# SCH_VFD_Driver_PT6315_2025-07-27.net
KiCad netlist of a schematic drawn in EasyEDA
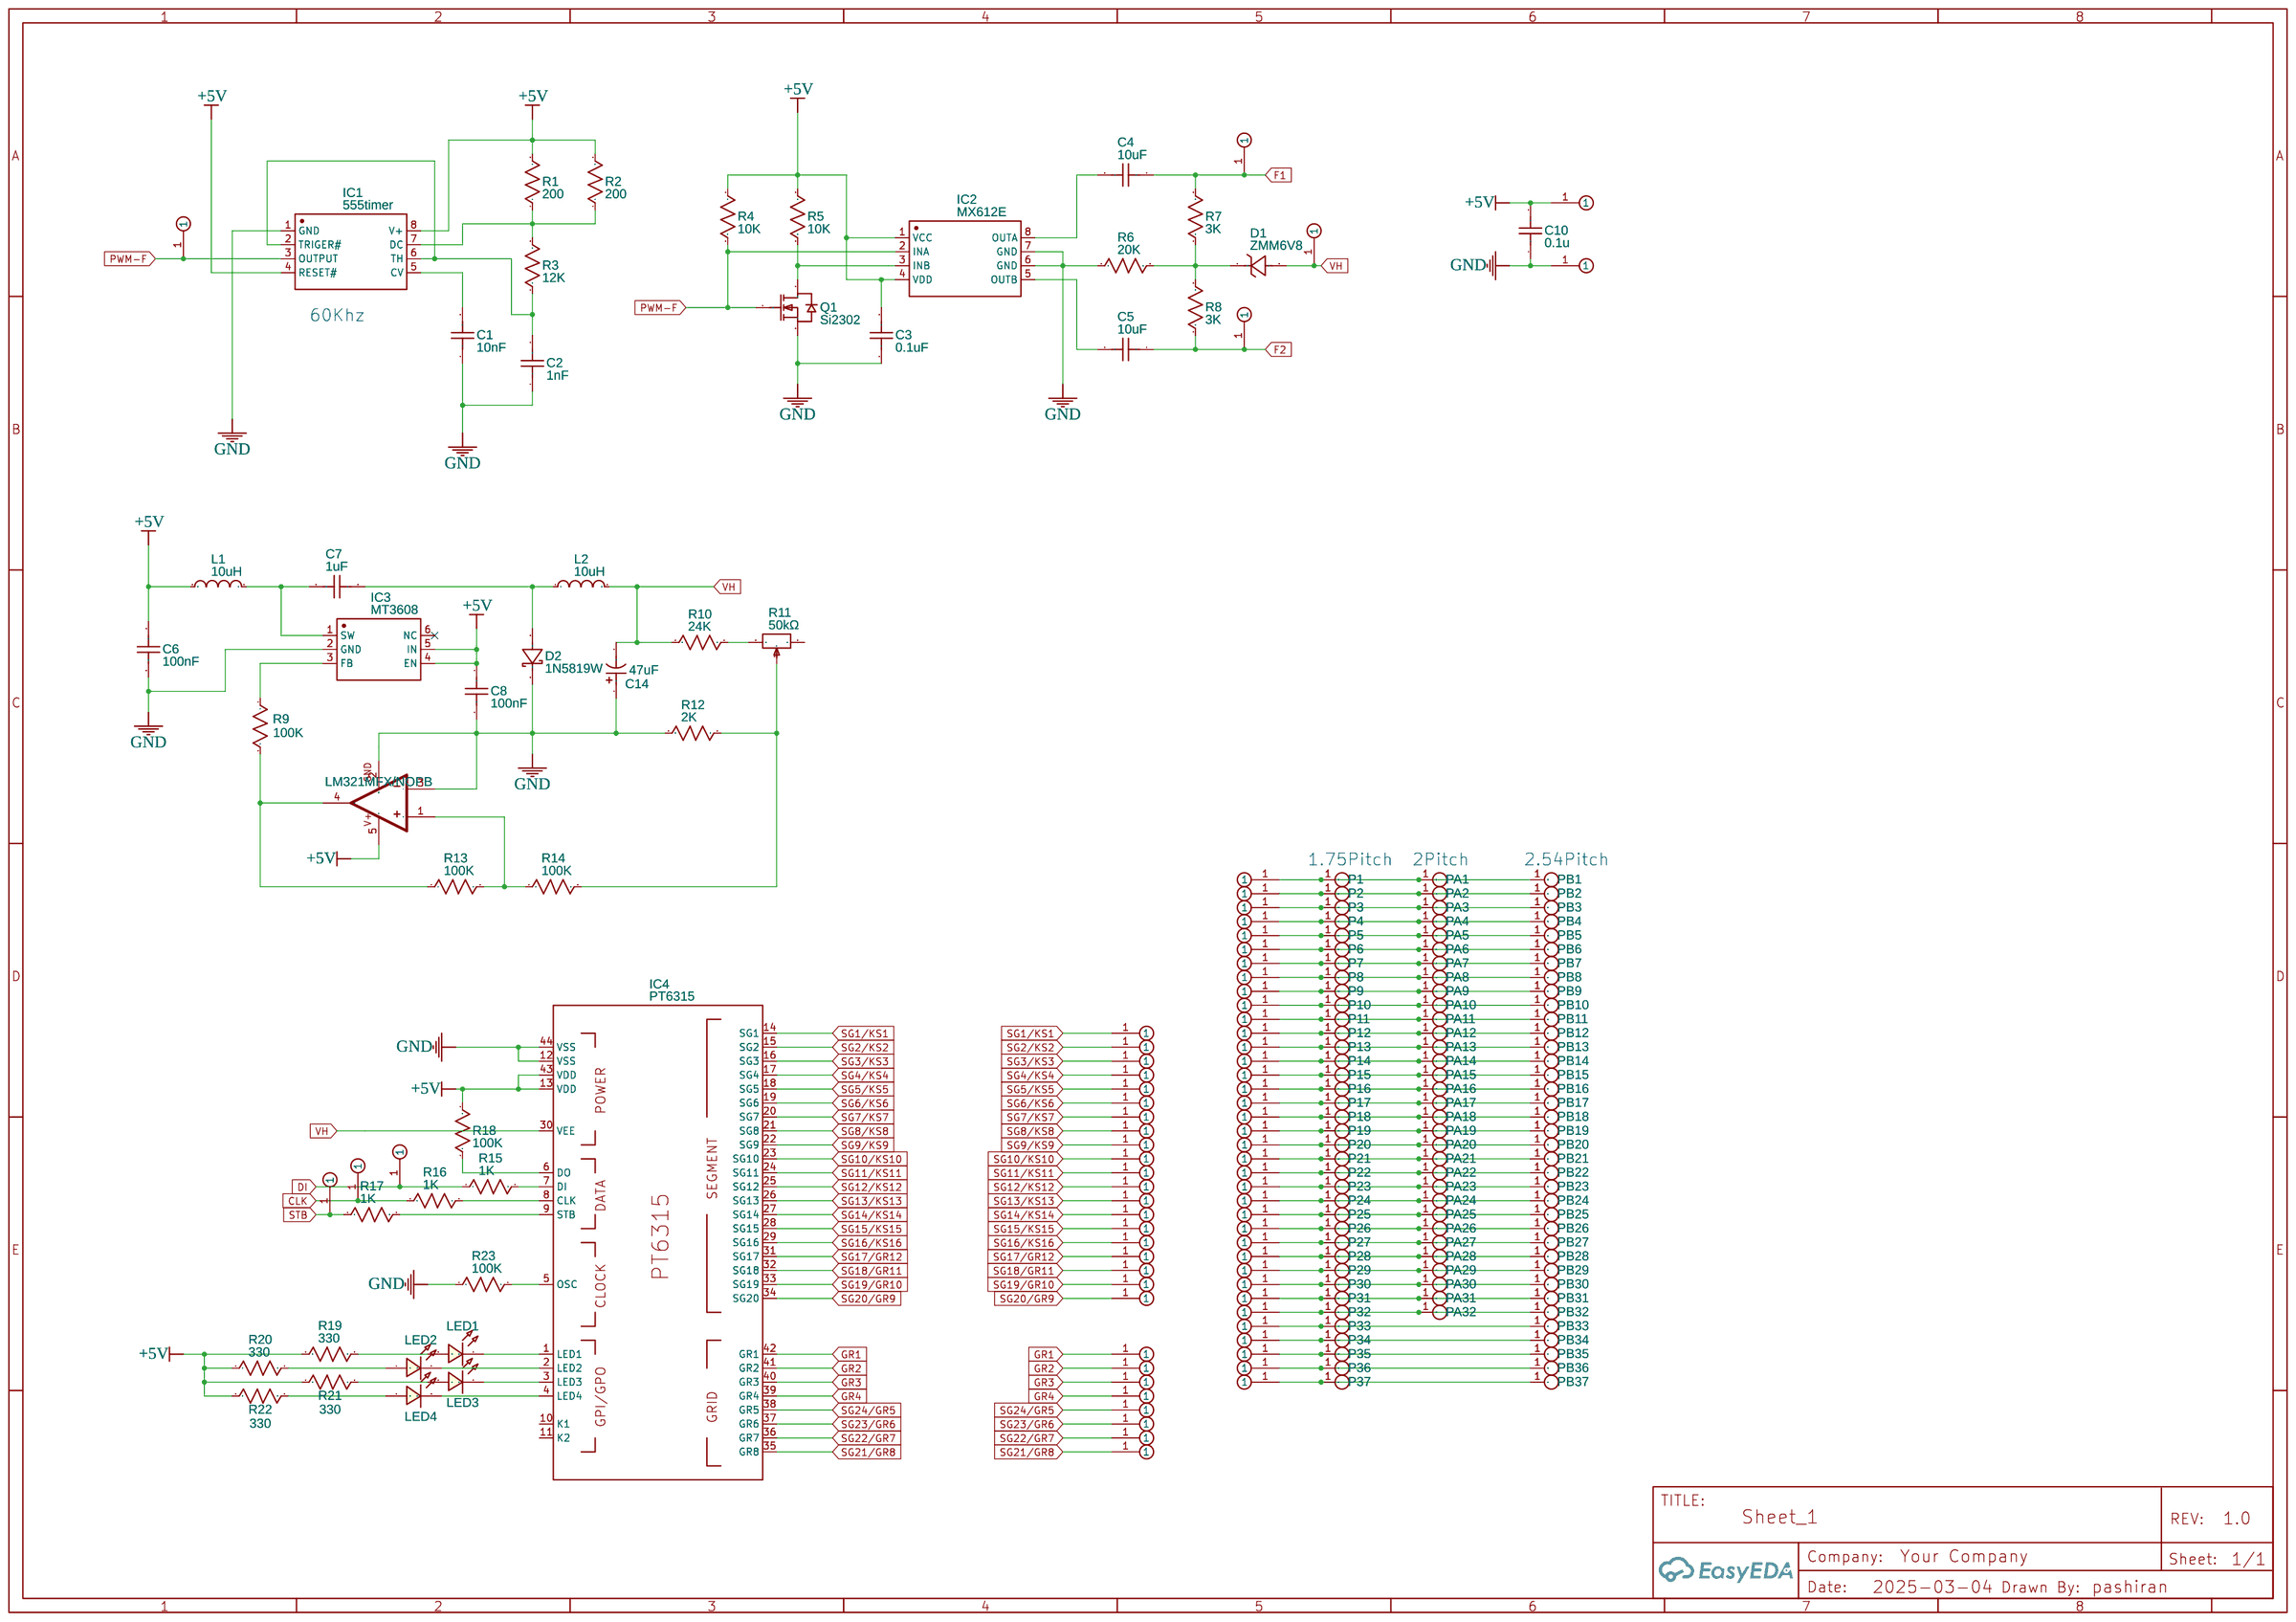
[diagram p0: schematic sheet]

(export (version "E")
  (design (tool "Eeschema 10.0.6"))
  (components
    (comp (ref "C1") (value "10nF") (libsource (lib "") (part "C_0805_US")))
    (comp (ref "C2") (value "1nF") (libsource (lib "") (part "C_0805_US")))
    (comp (ref "C3") (value "0.1uF") (libsource (lib "") (part "C_0805_US")))
    (comp (ref "C4") (value "10uF") (libsource (lib "") (part "C_0805_US_3")))
    (comp (ref "C5") (value "10uF") (libsource (lib "") (part "C_0805_US_3")))
    (comp (ref "C6") (value "100nF") (libsource (lib "") (part "C_0805_US_2")))
    (comp (ref "C7") (value "1uF") (libsource (lib "") (part "C_0805_US_1")))
    (comp (ref "C8") (value "100nF") (libsource (lib "") (part "C_0805_US_2")))
    (comp (ref "C10") (value "0.1u") (libsource (lib "") (part "C_0805_US")))
    (comp (ref "C14")
      (value "47uF")
      (fields
        (field (name "Manufacturer Part") "FVH025ADA470M0654")
        (field (name "Manufacturer") "FOSAN(富捷/富信)")
      )
      (libsource (lib "") (part "FVH025ADA470M0654"))
    )
    (comp (ref "CLK") (value "SMD-PAD-Mini") (libsource (lib "") (part "SMD-PAD-Mini_7")))
    (comp (ref "D1")
      (value "ZMM6V8")
      (fields (field (name "Manufacturer") "HXY MOSFET(华轩阳电子)"))
      (libsource (lib "") (part "ZMM6V8_C5345995"))
    )
    (comp (ref "D2")
      (value "1N5819W")
      (fields (field (name "Manufacturer") "ZHIDE(志得)"))
      (libsource (lib "") (part "1N5819W_C2683619"))
    )
    (comp (ref "DI") (value "SMD-PAD-Mini") (libsource (lib "") (part "SMD-PAD-Mini_3")))
    (comp (ref "F1") (value "SMD-PAD-Mini") (libsource (lib "") (part "SMD-PAD-Mini_6")))
    (comp (ref "F2") (value "SMD-PAD-Mini") (libsource (lib "") (part "SMD-PAD-Mini_6")))
    (comp (ref "GND") (value "SMD-PAD-Mini") (libsource (lib "") (part "SMD-PAD-Mini_4")))
    (comp (ref "IC1")
      (value "555timer")
      (fields (field (name "Manufacturer Part") "LMC555CMX/NOPB") (field (name "Manufacturer") "TI(德州仪器)"))
      (libsource (lib "") (part "LMC555CMX/NOPB"))
    )
    (comp (ref "IC2")
      (value "MX612E")
      (fields (field (name "Manufacturer") "Mixic(中科芯亿达)"))
      (libsource (lib "") (part "MX612E"))
    )
    (comp (ref "IC3")
      (value "MT3608")
      (fields (field (name "Manufacturer") "西安航天民芯"))
      (libsource (lib "") (part "MT3608"))
    )
    (comp (ref "IC4") (value "PT6315") (libsource (lib "") (part "PT6315")))
    (comp (ref "L1")
      (value "10uH")
      (fields (field (name "Manufacturer Part") "SMMS0420-100M") (field (name "Manufacturer") "SXN(顺翔诺)"))
      (libsource (lib "") (part "SMMS0420-100M_1"))
    )
    (comp (ref "L2")
      (value "10uH")
      (fields (field (name "Manufacturer Part") "SMMS0420-100M") (field (name "Manufacturer") "SXN(顺翔诺)"))
      (libsource (lib "") (part "SMMS0420-100M"))
    )
    (comp (ref "LED1")
      (value "LED-0805_R")
      (fields
        (field (name "Manufacturer Part") "17-21SURC/S530-A3/TR8")
        (field (name "Manufacturer") "EVERLIGHT(台湾亿光)")
      )
      (libsource (lib "") (part "LED-0805_R"))
    )
    (comp (ref "LED2")
      (value "LED-0805_R")
      (fields
        (field (name "Manufacturer Part") "17-21SURC/S530-A3/TR8")
        (field (name "Manufacturer") "EVERLIGHT(台湾亿光)")
      )
      (libsource (lib "") (part "LED-0805_R"))
    )
    (comp (ref "LED3")
      (value "LED-0805_R")
      (fields
        (field (name "Manufacturer Part") "17-21SURC/S530-A3/TR8")
        (field (name "Manufacturer") "EVERLIGHT(台湾亿光)")
      )
      (libsource (lib "") (part "LED-0805_R"))
    )
    (comp (ref "LED4")
      (value "LED-0805_R")
      (fields
        (field (name "Manufacturer Part") "17-21SURC/S530-A3/TR8")
        (field (name "Manufacturer") "EVERLIGHT(台湾亿光)")
      )
      (libsource (lib "") (part "LED-0805_R"))
    )
    (comp (ref "P1") (value "CON PAD") (libsource (lib "") (part "CON PAD_2")))
    (comp (ref "P2") (value "CON PAD") (libsource (lib "") (part "CON PAD_2")))
    (comp (ref "P3") (value "CON PAD") (libsource (lib "") (part "CON PAD_2")))
    (comp (ref "P4") (value "CON PAD") (libsource (lib "") (part "CON PAD_2")))
    (comp (ref "P5") (value "CON PAD") (libsource (lib "") (part "CON PAD_2")))
    (comp (ref "P6") (value "CON PAD") (libsource (lib "") (part "CON PAD_2")))
    (comp (ref "P7") (value "CON PAD") (libsource (lib "") (part "CON PAD_2")))
    (comp (ref "P8") (value "CON PAD") (libsource (lib "") (part "CON PAD_2")))
    (comp (ref "P9") (value "CON PAD") (libsource (lib "") (part "CON PAD_2")))
    (comp (ref "P10") (value "CON PAD") (libsource (lib "") (part "CON PAD_2")))
    (comp (ref "P11") (value "CON PAD") (libsource (lib "") (part "CON PAD_2")))
    (comp (ref "P12") (value "CON PAD") (libsource (lib "") (part "CON PAD_2")))
    (comp (ref "P13") (value "CON PAD") (libsource (lib "") (part "CON PAD_2")))
    (comp (ref "P14") (value "CON PAD") (libsource (lib "") (part "CON PAD_2")))
    (comp (ref "P15") (value "CON PAD") (libsource (lib "") (part "CON PAD_2")))
    (comp (ref "P16") (value "CON PAD") (libsource (lib "") (part "CON PAD_2")))
    (comp (ref "P17") (value "CON PAD") (libsource (lib "") (part "CON PAD_2")))
    (comp (ref "P18") (value "CON PAD") (libsource (lib "") (part "CON PAD_2")))
    (comp (ref "P19") (value "CON PAD") (libsource (lib "") (part "CON PAD_2")))
    (comp (ref "P20") (value "CON PAD") (libsource (lib "") (part "CON PAD_2")))
    (comp (ref "P21") (value "CON PAD") (libsource (lib "") (part "CON PAD_2")))
    (comp (ref "P22") (value "CON PAD") (libsource (lib "") (part "CON PAD_2")))
    (comp (ref "P23") (value "CON PAD") (libsource (lib "") (part "CON PAD_2")))
    (comp (ref "P24") (value "CON PAD") (libsource (lib "") (part "CON PAD_2")))
    (comp (ref "P25") (value "CON PAD") (libsource (lib "") (part "CON PAD_2")))
    (comp (ref "P26") (value "CON PAD") (libsource (lib "") (part "CON PAD_2")))
    (comp (ref "P27") (value "CON PAD") (libsource (lib "") (part "CON PAD_2")))
    (comp (ref "P28") (value "CON PAD") (libsource (lib "") (part "CON PAD_2")))
    (comp (ref "P29") (value "CON PAD") (libsource (lib "") (part "CON PAD_2")))
    (comp (ref "P30") (value "CON PAD") (libsource (lib "") (part "CON PAD_2")))
    (comp (ref "P31") (value "CON PAD") (libsource (lib "") (part "CON PAD_2")))
    (comp (ref "P32") (value "CON PAD") (libsource (lib "") (part "CON PAD_2")))
    (comp (ref "P33") (value "CON PAD") (libsource (lib "") (part "CON PAD_2")))
    (comp (ref "P34") (value "CON PAD") (libsource (lib "") (part "CON PAD_2")))
    (comp (ref "P35") (value "CON PAD") (libsource (lib "") (part "CON PAD_2")))
    (comp (ref "P36") (value "CON PAD") (libsource (lib "") (part "CON PAD_2")))
    (comp (ref "P37") (value "CON PAD") (libsource (lib "") (part "CON PAD_2")))
    (comp (ref "PA1") (value "CON PAD") (libsource (lib "") (part "CON PAD")))
    (comp (ref "PA2") (value "CON PAD") (libsource (lib "") (part "CON PAD")))
    (comp (ref "PA3") (value "CON PAD") (libsource (lib "") (part "CON PAD")))
    (comp (ref "PA4") (value "CON PAD") (libsource (lib "") (part "CON PAD")))
    (comp (ref "PA5") (value "CON PAD") (libsource (lib "") (part "CON PAD")))
    (comp (ref "PA6") (value "CON PAD") (libsource (lib "") (part "CON PAD")))
    (comp (ref "PA7") (value "CON PAD") (libsource (lib "") (part "CON PAD")))
    (comp (ref "PA8") (value "CON PAD") (libsource (lib "") (part "CON PAD")))
    (comp (ref "PA9") (value "CON PAD") (libsource (lib "") (part "CON PAD")))
    (comp (ref "PA10") (value "CON PAD") (libsource (lib "") (part "CON PAD")))
    (comp (ref "PA11") (value "CON PAD") (libsource (lib "") (part "CON PAD")))
    (comp (ref "PA12") (value "CON PAD") (libsource (lib "") (part "CON PAD")))
    (comp (ref "PA13") (value "CON PAD") (libsource (lib "") (part "CON PAD")))
    (comp (ref "PA14") (value "CON PAD") (libsource (lib "") (part "CON PAD")))
    (comp (ref "PA15") (value "CON PAD") (libsource (lib "") (part "CON PAD")))
    (comp (ref "PA16") (value "CON PAD") (libsource (lib "") (part "CON PAD")))
    (comp (ref "PA17") (value "CON PAD") (libsource (lib "") (part "CON PAD")))
    (comp (ref "PA18") (value "CON PAD") (libsource (lib "") (part "CON PAD")))
    (comp (ref "PA19") (value "CON PAD") (libsource (lib "") (part "CON PAD")))
    (comp (ref "PA20") (value "CON PAD") (libsource (lib "") (part "CON PAD")))
    (comp (ref "PA21") (value "CON PAD") (libsource (lib "") (part "CON PAD")))
    (comp (ref "PA22") (value "CON PAD") (libsource (lib "") (part "CON PAD")))
    (comp (ref "PA23") (value "CON PAD") (libsource (lib "") (part "CON PAD")))
    (comp (ref "PA24") (value "CON PAD") (libsource (lib "") (part "CON PAD")))
    (comp (ref "PA25") (value "CON PAD") (libsource (lib "") (part "CON PAD")))
    (comp (ref "PA26") (value "CON PAD") (libsource (lib "") (part "CON PAD")))
    (comp (ref "PA27") (value "CON PAD") (libsource (lib "") (part "CON PAD")))
    (comp (ref "PA28") (value "CON PAD") (libsource (lib "") (part "CON PAD")))
    (comp (ref "PA29") (value "CON PAD") (libsource (lib "") (part "CON PAD")))
    (comp (ref "PA30") (value "CON PAD") (libsource (lib "") (part "CON PAD")))
    (comp (ref "PA31") (value "CON PAD") (libsource (lib "") (part "CON PAD")))
    (comp (ref "PA32") (value "CON PAD") (libsource (lib "") (part "CON PAD")))
    (comp (ref "PB1") (value "CON PAD") (libsource (lib "") (part "CON PAD_1")))
    (comp (ref "PB2") (value "CON PAD") (libsource (lib "") (part "CON PAD_1")))
    (comp (ref "PB3") (value "CON PAD") (libsource (lib "") (part "CON PAD_1")))
    (comp (ref "PB4") (value "CON PAD") (libsource (lib "") (part "CON PAD_1")))
    (comp (ref "PB5") (value "CON PAD") (libsource (lib "") (part "CON PAD_1")))
    (comp (ref "PB6") (value "CON PAD") (libsource (lib "") (part "CON PAD_1")))
    (comp (ref "PB7") (value "CON PAD") (libsource (lib "") (part "CON PAD_1")))
    (comp (ref "PB8") (value "CON PAD") (libsource (lib "") (part "CON PAD_1")))
    (comp (ref "PB9") (value "CON PAD") (libsource (lib "") (part "CON PAD_1")))
    (comp (ref "PB10") (value "CON PAD") (libsource (lib "") (part "CON PAD_1")))
    (comp (ref "PB11") (value "CON PAD") (libsource (lib "") (part "CON PAD_1")))
    (comp (ref "PB12") (value "CON PAD") (libsource (lib "") (part "CON PAD_1")))
    (comp (ref "PB13") (value "CON PAD") (libsource (lib "") (part "CON PAD_1")))
    (comp (ref "PB14") (value "CON PAD") (libsource (lib "") (part "CON PAD_1")))
    (comp (ref "PB15") (value "CON PAD") (libsource (lib "") (part "CON PAD_1")))
    (comp (ref "PB16") (value "CON PAD") (libsource (lib "") (part "CON PAD_1")))
    (comp (ref "PB17") (value "CON PAD") (libsource (lib "") (part "CON PAD_1")))
    (comp (ref "PB18") (value "CON PAD") (libsource (lib "") (part "CON PAD_1")))
    (comp (ref "PB19") (value "CON PAD") (libsource (lib "") (part "CON PAD_1")))
    (comp (ref "PB20") (value "CON PAD") (libsource (lib "") (part "CON PAD_1")))
    (comp (ref "PB21") (value "CON PAD") (libsource (lib "") (part "CON PAD_1")))
    (comp (ref "PB22") (value "CON PAD") (libsource (lib "") (part "CON PAD_1")))
    (comp (ref "PB23") (value "CON PAD") (libsource (lib "") (part "CON PAD_1")))
    (comp (ref "PB24") (value "CON PAD") (libsource (lib "") (part "CON PAD_1")))
    (comp (ref "PB25") (value "CON PAD") (libsource (lib "") (part "CON PAD_1")))
    (comp (ref "PB26") (value "CON PAD") (libsource (lib "") (part "CON PAD_1")))
    (comp (ref "PB27") (value "CON PAD") (libsource (lib "") (part "CON PAD_1")))
    (comp (ref "PB28") (value "CON PAD") (libsource (lib "") (part "CON PAD_1")))
    (comp (ref "PB29") (value "CON PAD") (libsource (lib "") (part "CON PAD_1")))
    (comp (ref "PB30") (value "CON PAD") (libsource (lib "") (part "CON PAD_1")))
    (comp (ref "PB31") (value "CON PAD") (libsource (lib "") (part "CON PAD_1")))
    (comp (ref "PB32") (value "CON PAD") (libsource (lib "") (part "CON PAD_1")))
    (comp (ref "PB33") (value "CON PAD") (libsource (lib "") (part "CON PAD_1")))
    (comp (ref "PB34") (value "CON PAD") (libsource (lib "") (part "CON PAD_1")))
    (comp (ref "PB35") (value "CON PAD") (libsource (lib "") (part "CON PAD_1")))
    (comp (ref "PB36") (value "CON PAD") (libsource (lib "") (part "CON PAD_1")))
    (comp (ref "PB37") (value "CON PAD") (libsource (lib "") (part "CON PAD_1")))
    (comp (ref "PWM") (value "SMD-PAD-Mini") (libsource (lib "") (part "SMD-PAD-Mini_9")))
    (comp (ref "Q1")
      (value "Si2302")
      (fields
        (field (name "Manufacturer Part") "Si2302CDS-T1-GE3")
        (field (name "Manufacturer") "VISHAY(威世)")
      )
      (libsource (lib "") (part "Si2302CDS-T1-GE3"))
    )
    (comp (ref "R1") (value "200") (libsource (lib "") (part "R_0805_US")))
    (comp (ref "R2") (value "200") (libsource (lib "") (part "R_0805_US")))
    (comp (ref "R3") (value "12K") (libsource (lib "") (part "R_0805_US")))
    (comp (ref "R4") (value "10K") (libsource (lib "") (part "R_0805_US_1")))
    (comp (ref "R5") (value "10K") (libsource (lib "") (part "R_0805_US_1")))
    (comp (ref "R6") (value "20K") (libsource (lib "") (part "R_0805_US_2")))
    (comp (ref "R7") (value "3K") (libsource (lib "") (part "R_0805_US")))
    (comp (ref "R8") (value "3K") (libsource (lib "") (part "R_0805_US")))
    (comp (ref "R9") (value "100K") (libsource (lib "") (part "R_0805_US_1")))
    (comp (ref "R10") (value "24K") (libsource (lib "") (part "R_0805_US_2")))
    (comp (ref "R11")
      (value "50kΩ")
      (fields (field (name "Manufacturer Part") "VG039NCHXTB503") (field (name "Manufacturer") "HDK(北陆电气)"))
      (libsource (lib "") (part "VG039NCHXTB503"))
    )
    (comp (ref "R12") (value "2K") (libsource (lib "") (part "R_0805_US_3")))
    (comp (ref "R13") (value "100K") (libsource (lib "") (part "R_0805_US_2")))
    (comp (ref "R14") (value "100K") (libsource (lib "") (part "R_0805_US_2")))
    (comp (ref "R15") (value "1K") (libsource (lib "") (part "R_0805_US_2")))
    (comp (ref "R16") (value "1K") (libsource (lib "") (part "R_0805_US_2")))
    (comp (ref "R17") (value "1K") (libsource (lib "") (part "R_0805_US_2")))
    (comp (ref "R18") (value "100K") (libsource (lib "") (part "R_0805_US")))
    (comp (ref "R19") (value "330") (libsource (lib "") (part "R_0805_US_2")))
    (comp (ref "R20") (value "330") (libsource (lib "") (part "R_0805_US_2")))
    (comp (ref "R21") (value "330") (libsource (lib "") (part "R_0805_US_2")))
    (comp (ref "R22") (value "330") (libsource (lib "") (part "R_0805_US_2")))
    (comp (ref "R23") (value "100K") (libsource (lib "") (part "R_0805_US_2")))
    (comp (ref "STB") (value "SMD-PAD-Mini") (libsource (lib "") (part "SMD-PAD-Mini_5")))
    (comp (ref "U1") (value "SMD-PAD-Mini") (libsource (lib "") (part "SMD-PAD-Mini_1")))
    (comp (ref "U2") (value "SMD-PAD-Mini") (libsource (lib "") (part "SMD-PAD-Mini_1")))
    (comp (ref "U3") (value "SMD-PAD-Mini") (libsource (lib "") (part "SMD-PAD-Mini_1")))
    (comp (ref "U4") (value "SMD-PAD-Mini") (libsource (lib "") (part "SMD-PAD-Mini_1")))
    (comp (ref "U5") (value "SMD-PAD-Mini") (libsource (lib "") (part "SMD-PAD-Mini_1")))
    (comp (ref "U6") (value "SMD-PAD-Mini") (libsource (lib "") (part "SMD-PAD-Mini_1")))
    (comp (ref "U7") (value "SMD-PAD-Mini") (libsource (lib "") (part "SMD-PAD-Mini_1")))
    (comp (ref "U8") (value "SMD-PAD-Mini") (libsource (lib "") (part "SMD-PAD-Mini_1")))
    (comp (ref "U9") (value "SMD-PAD-Mini") (libsource (lib "") (part "SMD-PAD-Mini_1")))
    (comp (ref "U10") (value "SMD-PAD-Mini") (libsource (lib "") (part "SMD-PAD-Mini_1")))
    (comp (ref "U11") (value "SMD-PAD-Mini") (libsource (lib "") (part "SMD-PAD-Mini_1")))
    (comp (ref "U12") (value "SMD-PAD-Mini") (libsource (lib "") (part "SMD-PAD-Mini_1")))
    (comp (ref "U13") (value "SMD-PAD-Mini") (libsource (lib "") (part "SMD-PAD-Mini_1")))
    (comp (ref "U14") (value "SMD-PAD-Mini") (libsource (lib "") (part "SMD-PAD-Mini_1")))
    (comp (ref "U15") (value "SMD-PAD-Mini") (libsource (lib "") (part "SMD-PAD-Mini_1")))
    (comp (ref "U16") (value "SMD-PAD-Mini") (libsource (lib "") (part "SMD-PAD-Mini_1")))
    (comp (ref "U17") (value "SMD-PAD-Mini") (libsource (lib "") (part "SMD-PAD-Mini_1")))
    (comp (ref "U18") (value "SMD-PAD-Mini") (libsource (lib "") (part "SMD-PAD-Mini_1")))
    (comp (ref "U19") (value "SMD-PAD-Mini") (libsource (lib "") (part "SMD-PAD-Mini_1")))
    (comp (ref "U20") (value "SMD-PAD-Mini") (libsource (lib "") (part "SMD-PAD-Mini_1")))
    (comp (ref "U21") (value "SMD-PAD-Mini") (libsource (lib "") (part "SMD-PAD-Mini_1")))
    (comp (ref "U22") (value "SMD-PAD-Mini") (libsource (lib "") (part "SMD-PAD-Mini_1")))
    (comp (ref "U23") (value "SMD-PAD-Mini") (libsource (lib "") (part "SMD-PAD-Mini_1")))
    (comp (ref "U24") (value "SMD-PAD-Mini") (libsource (lib "") (part "SMD-PAD-Mini_1")))
    (comp (ref "U25") (value "SMD-PAD-Mini") (libsource (lib "") (part "SMD-PAD-Mini_1")))
    (comp (ref "U26") (value "SMD-PAD-Mini") (libsource (lib "") (part "SMD-PAD-Mini_1")))
    (comp (ref "U27") (value "SMD-PAD-Mini") (libsource (lib "") (part "SMD-PAD-Mini_1")))
    (comp (ref "U28") (value "SMD-PAD-Mini") (libsource (lib "") (part "SMD-PAD-Mini_1")))
    (comp (ref "U29") (value "SMD-PAD-Mini") (libsource (lib "") (part "SMD-PAD-Mini")))
    (comp (ref "U30") (value "SMD-PAD-Mini") (libsource (lib "") (part "SMD-PAD-Mini")))
    (comp (ref "U31") (value "SMD-PAD-Mini") (libsource (lib "") (part "SMD-PAD-Mini")))
    (comp (ref "U32") (value "SMD-PAD-Mini") (libsource (lib "") (part "SMD-PAD-Mini")))
    (comp (ref "U33") (value "SMD-PAD-Mini") (libsource (lib "") (part "SMD-PAD-Mini")))
    (comp (ref "U34") (value "SMD-PAD-Mini") (libsource (lib "") (part "SMD-PAD-Mini")))
    (comp (ref "U35") (value "SMD-PAD-Mini") (libsource (lib "") (part "SMD-PAD-Mini")))
    (comp (ref "U36") (value "SMD-PAD-Mini") (libsource (lib "") (part "SMD-PAD-Mini")))
    (comp (ref "U37") (value "SMD-PAD-Mini") (libsource (lib "") (part "SMD-PAD-Mini")))
    (comp (ref "U38") (value "SMD-PAD-Mini") (libsource (lib "") (part "SMD-PAD-Mini")))
    (comp (ref "U39") (value "SMD-PAD-Mini") (libsource (lib "") (part "SMD-PAD-Mini")))
    (comp (ref "U40") (value "SMD-PAD-Mini") (libsource (lib "") (part "SMD-PAD-Mini")))
    (comp (ref "U41") (value "SMD-PAD-Mini") (libsource (lib "") (part "SMD-PAD-Mini")))
    (comp (ref "U42") (value "SMD-PAD-Mini") (libsource (lib "") (part "SMD-PAD-Mini")))
    (comp (ref "U43") (value "SMD-PAD-Mini") (libsource (lib "") (part "SMD-PAD-Mini")))
    (comp (ref "U44") (value "SMD-PAD-Mini") (libsource (lib "") (part "SMD-PAD-Mini")))
    (comp (ref "U45") (value "SMD-PAD-Mini") (libsource (lib "") (part "SMD-PAD-Mini")))
    (comp (ref "U46") (value "SMD-PAD-Mini") (libsource (lib "") (part "SMD-PAD-Mini")))
    (comp (ref "U47") (value "SMD-PAD-Mini") (libsource (lib "") (part "SMD-PAD-Mini")))
    (comp (ref "U48") (value "SMD-PAD-Mini") (libsource (lib "") (part "SMD-PAD-Mini")))
    (comp (ref "U49") (value "SMD-PAD-Mini") (libsource (lib "") (part "SMD-PAD-Mini")))
    (comp (ref "U50") (value "SMD-PAD-Mini") (libsource (lib "") (part "SMD-PAD-Mini")))
    (comp (ref "U51") (value "SMD-PAD-Mini") (libsource (lib "") (part "SMD-PAD-Mini")))
    (comp (ref "U52") (value "SMD-PAD-Mini") (libsource (lib "") (part "SMD-PAD-Mini")))
    (comp (ref "U53") (value "SMD-PAD-Mini") (libsource (lib "") (part "SMD-PAD-Mini")))
    (comp (ref "U54") (value "SMD-PAD-Mini") (libsource (lib "") (part "SMD-PAD-Mini")))
    (comp (ref "U55") (value "SMD-PAD-Mini") (libsource (lib "") (part "SMD-PAD-Mini")))
    (comp (ref "U56") (value "SMD-PAD-Mini") (libsource (lib "") (part "SMD-PAD-Mini")))
    (comp (ref "U57") (value "SMD-PAD-Mini") (libsource (lib "") (part "SMD-PAD-Mini")))
    (comp (ref "U58") (value "SMD-PAD-Mini") (libsource (lib "") (part "SMD-PAD-Mini")))
    (comp (ref "U59") (value "SMD-PAD-Mini") (libsource (lib "") (part "SMD-PAD-Mini")))
    (comp (ref "U60") (value "SMD-PAD-Mini") (libsource (lib "") (part "SMD-PAD-Mini")))
    (comp (ref "U61") (value "SMD-PAD-Mini") (libsource (lib "") (part "SMD-PAD-Mini")))
    (comp (ref "U62") (value "SMD-PAD-Mini") (libsource (lib "") (part "SMD-PAD-Mini")))
    (comp (ref "U63") (value "SMD-PAD-Mini") (libsource (lib "") (part "SMD-PAD-Mini")))
    (comp (ref "U64") (value "SMD-PAD-Mini") (libsource (lib "") (part "SMD-PAD-Mini")))
    (comp (ref "U65") (value "SMD-PAD-Mini") (libsource (lib "") (part "SMD-PAD-Mini")))
    (comp (ref "U67")
      (value "LM321MFX/NOPB")
      (fields (field (name "Manufacturer") "TI(德州仪器)"))
      (libsource (lib "") (part "LM321MFX/NOPB"))
    )
    (comp (ref "VCC") (value "SMD-PAD-Mini") (libsource (lib "") (part "SMD-PAD-Mini_8")))
    (comp (ref "VH") (value "SMD-PAD-Mini") (libsource (lib "") (part "SMD-PAD-Mini_2")))
  )
  (nets
    (net (code "1") (name "+5V") (class "Default")
      (node (ref "C10") (pin "2") (pinfunction "2_2") (pintype "unspecified"))
      (node (ref "C3") (pin "2") (pinfunction "2_2") (pintype "unspecified"))
      (node (ref "C6") (pin "1") (pinfunction "1_1") (pintype "unspecified"))
      (node (ref "C8") (pin "1") (pinfunction "1_1") (pintype "unspecified"))
      (node (ref "IC1") (pin "4") (pinfunction "RESET#_4") (pintype "unspecified"))
      (node (ref "IC1") (pin "8") (pinfunction "V+_8") (pintype "unspecified"))
      (node (ref "IC2") (pin "1") (pinfunction "VCC_1") (pintype "unspecified"))
      (node (ref "IC2") (pin "4") (pinfunction "VDD_4") (pintype "unspecified"))
      (node (ref "IC3") (pin "4") (pinfunction "EN_4") (pintype "unspecified"))
      (node (ref "IC3") (pin "5") (pinfunction "IN_5") (pintype "unspecified"))
      (node (ref "IC4") (pin "13") (pinfunction "VDD_13") (pintype "unspecified"))
      (node (ref "IC4") (pin "43") (pinfunction "VDD_43") (pintype "unspecified"))
      (node (ref "L1") (pin "1") (pinfunction "1_1") (pintype "unspecified"))
      (node (ref "R1") (pin "2") (pinfunction "2_2") (pintype "unspecified"))
      (node (ref "R18") (pin "2") (pinfunction "2_2") (pintype "unspecified"))
      (node (ref "R19") (pin "1") (pinfunction "1_1") (pintype "unspecified"))
      (node (ref "R2") (pin "2") (pinfunction "2_2") (pintype "unspecified"))
      (node (ref "R20") (pin "1") (pinfunction "1_1") (pintype "unspecified"))
      (node (ref "R21") (pin "1") (pinfunction "1_1") (pintype "unspecified"))
      (node (ref "R22") (pin "1") (pinfunction "1_1") (pintype "unspecified"))
      (node (ref "R4") (pin "1") (pinfunction "1_1") (pintype "unspecified"))
      (node (ref "R5") (pin "1") (pinfunction "1_1") (pintype "unspecified"))
      (node (ref "U67") (pin "5") (pinfunction "V+_5") (pintype "unspecified"))
      (node (ref "VCC") (pin "1") (pinfunction "1_1") (pintype "unspecified"))
    )
    (net (code "2") (name "CLK") (class "Default")
      (node (ref "CLK") (pin "1") (pinfunction "1_1") (pintype "unspecified"))
      (node (ref "R16") (pin "1") (pinfunction "1_1") (pintype "unspecified"))
    )
    (net (code "3") (name "DI") (class "Default")
      (node (ref "DI") (pin "1") (pinfunction "1_1") (pintype "unspecified"))
      (node (ref "R15") (pin "1") (pinfunction "1_1") (pintype "unspecified"))
    )
    (net (code "4") (name "F1") (class "Default")
      (node (ref "C4") (pin "1") (pinfunction "1_1") (pintype "unspecified"))
      (node (ref "F1") (pin "1") (pinfunction "1_1") (pintype "unspecified"))
      (node (ref "R7") (pin "2") (pinfunction "2_2") (pintype "unspecified"))
    )
    (net (code "5") (name "F2") (class "Default")
      (node (ref "C5") (pin "1") (pinfunction "1_1") (pintype "unspecified"))
      (node (ref "F2") (pin "1") (pinfunction "1_1") (pintype "unspecified"))
      (node (ref "R8") (pin "1") (pinfunction "1_1") (pintype "unspecified"))
    )
    (net (code "6") (name "GND") (class "Default")
      (node (ref "C1") (pin "1") (pinfunction "1_1") (pintype "unspecified"))
      (node (ref "C10") (pin "1") (pinfunction "1_1") (pintype "unspecified"))
      (node (ref "C14") (pin "1") (pinfunction "1_1") (pintype "input"))
      (node (ref "C2") (pin "1") (pinfunction "1_1") (pintype "unspecified"))
      (node (ref "C3") (pin "1") (pinfunction "1_1") (pintype "unspecified"))
      (node (ref "C6") (pin "2") (pinfunction "2_2") (pintype "unspecified"))
      (node (ref "C8") (pin "2") (pinfunction "2_2") (pintype "unspecified"))
      (node (ref "D2") (pin "2") (pinfunction "K_2") (pintype "unspecified"))
      (node (ref "GND") (pin "1") (pinfunction "1_1") (pintype "unspecified"))
      (node (ref "IC1") (pin "1") (pinfunction "GND_1") (pintype "unspecified"))
      (node (ref "IC2") (pin "6") (pinfunction "GND_6") (pintype "unspecified"))
      (node (ref "IC2") (pin "7") (pinfunction "GND_7") (pintype "unspecified"))
      (node (ref "IC3") (pin "2") (pinfunction "GND_2") (pintype "unspecified"))
      (node (ref "IC4") (pin "12") (pinfunction "VSS_12") (pintype "unspecified"))
      (node (ref "IC4") (pin "44") (pinfunction "VSS_44") (pintype "unspecified"))
      (node (ref "Q1") (pin "2") (pinfunction "S_2") (pintype "unspecified"))
      (node (ref "R12") (pin "2") (pinfunction "2_2") (pintype "unspecified"))
      (node (ref "R23") (pin "1") (pinfunction "1_1") (pintype "unspecified"))
      (node (ref "R6") (pin "1") (pinfunction "1_1") (pintype "unspecified"))
      (node (ref "U67") (pin "2") (pinfunction "GND_2") (pintype "unspecified"))
      (node (ref "U67") (pin "3") (pinfunction "-_3") (pintype "input"))
    )
    (net (code "7") (name "GR1") (class "Default")
      (node (ref "IC4") (pin "42") (pinfunction "GR1_42") (pintype "unspecified"))
      (node (ref "U21") (pin "1") (pinfunction "1_1") (pintype "unspecified"))
    )
    (net (code "8") (name "GR2") (class "Default")
      (node (ref "IC4") (pin "41") (pinfunction "GR2_41") (pintype "unspecified"))
      (node (ref "U22") (pin "1") (pinfunction "1_1") (pintype "unspecified"))
    )
    (net (code "9") (name "GR3") (class "Default")
      (node (ref "IC4") (pin "40") (pinfunction "GR3_40") (pintype "unspecified"))
      (node (ref "U23") (pin "1") (pinfunction "1_1") (pintype "unspecified"))
    )
    (net (code "10") (name "GR4") (class "Default")
      (node (ref "IC4") (pin "39") (pinfunction "GR4_39") (pintype "unspecified"))
      (node (ref "U24") (pin "1") (pinfunction "1_1") (pintype "unspecified"))
    )
    (net (code "11") (name "Net-(D1-C)") (class "Default")
      (node (ref "D1") (pin "1") (pinfunction "C_1") (pintype "unspecified"))
      (node (ref "R6") (pin "2") (pinfunction "2_2") (pintype "unspecified"))
      (node (ref "R7") (pin "1") (pinfunction "1_1") (pintype "unspecified"))
      (node (ref "R8") (pin "2") (pinfunction "2_2") (pintype "unspecified"))
    )
    (net (code "12") (name "Net-(D2-A)") (class "Default")
      (node (ref "C7") (pin "2") (pinfunction "2_2") (pintype "unspecified"))
      (node (ref "D2") (pin "1") (pinfunction "A_1") (pintype "unspecified"))
      (node (ref "L2") (pin "1") (pinfunction "1_1") (pintype "unspecified"))
    )
    (net (code "13") (name "Net-(IC1-CV)") (class "Default")
      (node (ref "C1") (pin "2") (pinfunction "2_2") (pintype "unspecified"))
      (node (ref "IC1") (pin "5") (pinfunction "CV_5") (pintype "unspecified"))
    )
    (net (code "14") (name "Net-(IC1-DC)") (class "Default")
      (node (ref "IC1") (pin "7") (pinfunction "DC_7") (pintype "unspecified"))
      (node (ref "R1") (pin "1") (pinfunction "1_1") (pintype "unspecified"))
      (node (ref "R2") (pin "1") (pinfunction "1_1") (pintype "unspecified"))
      (node (ref "R3") (pin "2") (pinfunction "2_2") (pintype "unspecified"))
    )
    (net (code "15") (name "Net-(IC1-TH)") (class "Default")
      (node (ref "C2") (pin "2") (pinfunction "2_2") (pintype "unspecified"))
      (node (ref "IC1") (pin "2") (pinfunction "TRIGER#_2") (pintype "unspecified"))
      (node (ref "IC1") (pin "6") (pinfunction "TH_6") (pintype "unspecified"))
      (node (ref "R3") (pin "1") (pinfunction "1_1") (pintype "unspecified"))
    )
    (net (code "16") (name "Net-(IC2-INB)") (class "Default")
      (node (ref "IC2") (pin "3") (pinfunction "INB_3") (pintype "unspecified"))
      (node (ref "Q1") (pin "3") (pinfunction "D_3") (pintype "unspecified"))
      (node (ref "R5") (pin "2") (pinfunction "2_2") (pintype "unspecified"))
    )
    (net (code "17") (name "Net-(IC2-OUTA)") (class "Default")
      (node (ref "C4") (pin "2") (pinfunction "2_2") (pintype "unspecified"))
      (node (ref "IC2") (pin "8") (pinfunction "OUTA_8") (pintype "unspecified"))
    )
    (net (code "18") (name "Net-(IC2-OUTB)") (class "Default")
      (node (ref "C5") (pin "2") (pinfunction "2_2") (pintype "unspecified"))
      (node (ref "IC2") (pin "5") (pinfunction "OUTB_5") (pintype "unspecified"))
    )
    (net (code "19") (name "Net-(IC3-FB)") (class "Default")
      (node (ref "IC3") (pin "3") (pinfunction "FB_3") (pintype "unspecified"))
      (node (ref "R9") (pin "1") (pinfunction "1_1") (pintype "unspecified"))
    )
    (net (code "20") (name "Net-(IC3-SW)") (class "Default")
      (node (ref "C7") (pin "1") (pinfunction "1_1") (pintype "unspecified"))
      (node (ref "IC3") (pin "1") (pinfunction "SW_1") (pintype "unspecified"))
      (node (ref "L1") (pin "2") (pinfunction "2_2") (pintype "unspecified"))
    )
    (net (code "21") (name "Net-(IC4-CLK)") (class "Default")
      (node (ref "IC4") (pin "8") (pinfunction "CLK_8") (pintype "unspecified"))
      (node (ref "R16") (pin "2") (pinfunction "2_2") (pintype "unspecified"))
    )
    (net (code "22") (name "Net-(IC4-DI)") (class "Default")
      (node (ref "IC4") (pin "7") (pinfunction "DI_7") (pintype "unspecified"))
      (node (ref "R15") (pin "2") (pinfunction "2_2") (pintype "unspecified"))
    )
    (net (code "23") (name "Net-(IC4-DO)") (class "Default")
      (node (ref "IC4") (pin "6") (pinfunction "DO_6") (pintype "unspecified"))
      (node (ref "R18") (pin "1") (pinfunction "1_1") (pintype "unspecified"))
    )
    (net (code "24") (name "Net-(IC4-LED1)") (class "Default")
      (node (ref "IC4") (pin "1") (pinfunction "LED1_1") (pintype "unspecified"))
      (node (ref "LED1") (pin "2") (pinfunction "2_2") (pintype "unspecified"))
    )
    (net (code "25") (name "Net-(IC4-LED2)") (class "Default")
      (node (ref "IC4") (pin "2") (pinfunction "LED2_2") (pintype "unspecified"))
      (node (ref "LED2") (pin "2") (pinfunction "2_2") (pintype "unspecified"))
    )
    (net (code "26") (name "Net-(IC4-LED3)") (class "Default")
      (node (ref "IC4") (pin "3") (pinfunction "LED3_3") (pintype "unspecified"))
      (node (ref "LED3") (pin "2") (pinfunction "2_2") (pintype "unspecified"))
    )
    (net (code "27") (name "Net-(IC4-LED4)") (class "Default")
      (node (ref "IC4") (pin "4") (pinfunction "LED4_4") (pintype "unspecified"))
      (node (ref "LED4") (pin "2") (pinfunction "2_2") (pintype "unspecified"))
    )
    (net (code "28") (name "Net-(IC4-OSC)") (class "Default")
      (node (ref "IC4") (pin "5") (pinfunction "OSC_5") (pintype "unspecified"))
      (node (ref "R23") (pin "2") (pinfunction "2_2") (pintype "unspecified"))
    )
    (net (code "29") (name "Net-(IC4-STB)") (class "Default")
      (node (ref "IC4") (pin "9") (pinfunction "STB_9") (pintype "unspecified"))
      (node (ref "R17") (pin "2") (pinfunction "2_2") (pintype "unspecified"))
    )
    (net (code "30") (name "Net-(LED1-Pad1)") (class "Default")
      (node (ref "LED1") (pin "1") (pinfunction "1_1") (pintype "unspecified"))
      (node (ref "R19") (pin "2") (pinfunction "2_2") (pintype "unspecified"))
    )
    (net (code "31") (name "Net-(LED2-Pad1)") (class "Default")
      (node (ref "LED2") (pin "1") (pinfunction "1_1") (pintype "unspecified"))
      (node (ref "R20") (pin "2") (pinfunction "2_2") (pintype "unspecified"))
    )
    (net (code "32") (name "Net-(LED3-Pad1)") (class "Default")
      (node (ref "LED3") (pin "1") (pinfunction "1_1") (pintype "unspecified"))
      (node (ref "R21") (pin "2") (pinfunction "2_2") (pintype "unspecified"))
    )
    (net (code "33") (name "Net-(LED4-Pad1)") (class "Default")
      (node (ref "LED4") (pin "1") (pinfunction "1_1") (pintype "unspecified"))
      (node (ref "R22") (pin "2") (pinfunction "2_2") (pintype "unspecified"))
    )
    (net (code "34") (name "Net-(P1-Pad)") (class "Default")
      (node (ref "P1") (pin "1") (pinfunction "Pad_1") (pintype "unspecified"))
      (node (ref "PA1") (pin "1") (pinfunction "Pad_1") (pintype "unspecified"))
      (node (ref "PB1") (pin "1") (pinfunction "Pad_1") (pintype "unspecified"))
      (node (ref "U29") (pin "1") (pinfunction "1_1") (pintype "unspecified"))
    )
    (net (code "35") (name "Net-(P2-Pad)") (class "Default")
      (node (ref "P2") (pin "1") (pinfunction "Pad_1") (pintype "unspecified"))
      (node (ref "PA2") (pin "1") (pinfunction "Pad_1") (pintype "unspecified"))
      (node (ref "PB2") (pin "1") (pinfunction "Pad_1") (pintype "unspecified"))
      (node (ref "U30") (pin "1") (pinfunction "1_1") (pintype "unspecified"))
    )
    (net (code "36") (name "Net-(P3-Pad)") (class "Default")
      (node (ref "P3") (pin "1") (pinfunction "Pad_1") (pintype "unspecified"))
      (node (ref "PA3") (pin "1") (pinfunction "Pad_1") (pintype "unspecified"))
      (node (ref "PB3") (pin "1") (pinfunction "Pad_1") (pintype "unspecified"))
      (node (ref "U31") (pin "1") (pinfunction "1_1") (pintype "unspecified"))
    )
    (net (code "37") (name "Net-(P4-Pad)") (class "Default")
      (node (ref "P4") (pin "1") (pinfunction "Pad_1") (pintype "unspecified"))
      (node (ref "PA4") (pin "1") (pinfunction "Pad_1") (pintype "unspecified"))
      (node (ref "PB4") (pin "1") (pinfunction "Pad_1") (pintype "unspecified"))
      (node (ref "U32") (pin "1") (pinfunction "1_1") (pintype "unspecified"))
    )
    (net (code "38") (name "Net-(P5-Pad)") (class "Default")
      (node (ref "P5") (pin "1") (pinfunction "Pad_1") (pintype "unspecified"))
      (node (ref "PA5") (pin "1") (pinfunction "Pad_1") (pintype "unspecified"))
      (node (ref "PB5") (pin "1") (pinfunction "Pad_1") (pintype "unspecified"))
      (node (ref "U33") (pin "1") (pinfunction "1_1") (pintype "unspecified"))
    )
    (net (code "39") (name "Net-(P6-Pad)") (class "Default")
      (node (ref "P6") (pin "1") (pinfunction "Pad_1") (pintype "unspecified"))
      (node (ref "PA6") (pin "1") (pinfunction "Pad_1") (pintype "unspecified"))
      (node (ref "PB6") (pin "1") (pinfunction "Pad_1") (pintype "unspecified"))
      (node (ref "U34") (pin "1") (pinfunction "1_1") (pintype "unspecified"))
    )
    (net (code "40") (name "Net-(P7-Pad)") (class "Default")
      (node (ref "P7") (pin "1") (pinfunction "Pad_1") (pintype "unspecified"))
      (node (ref "PA7") (pin "1") (pinfunction "Pad_1") (pintype "unspecified"))
      (node (ref "PB7") (pin "1") (pinfunction "Pad_1") (pintype "unspecified"))
      (node (ref "U35") (pin "1") (pinfunction "1_1") (pintype "unspecified"))
    )
    (net (code "41") (name "Net-(P8-Pad)") (class "Default")
      (node (ref "P8") (pin "1") (pinfunction "Pad_1") (pintype "unspecified"))
      (node (ref "PA8") (pin "1") (pinfunction "Pad_1") (pintype "unspecified"))
      (node (ref "PB8") (pin "1") (pinfunction "Pad_1") (pintype "unspecified"))
      (node (ref "U36") (pin "1") (pinfunction "1_1") (pintype "unspecified"))
    )
    (net (code "42") (name "Net-(P9-Pad)") (class "Default")
      (node (ref "P9") (pin "1") (pinfunction "Pad_1") (pintype "unspecified"))
      (node (ref "PA9") (pin "1") (pinfunction "Pad_1") (pintype "unspecified"))
      (node (ref "PB9") (pin "1") (pinfunction "Pad_1") (pintype "unspecified"))
      (node (ref "U37") (pin "1") (pinfunction "1_1") (pintype "unspecified"))
    )
    (net (code "43") (name "Net-(P10-Pad)") (class "Default")
      (node (ref "P10") (pin "1") (pinfunction "Pad_1") (pintype "unspecified"))
      (node (ref "PA10") (pin "1") (pinfunction "Pad_1") (pintype "unspecified"))
      (node (ref "PB10") (pin "1") (pinfunction "Pad_1") (pintype "unspecified"))
      (node (ref "U38") (pin "1") (pinfunction "1_1") (pintype "unspecified"))
    )
    (net (code "44") (name "Net-(P11-Pad)") (class "Default")
      (node (ref "P11") (pin "1") (pinfunction "Pad_1") (pintype "unspecified"))
      (node (ref "PA11") (pin "1") (pinfunction "Pad_1") (pintype "unspecified"))
      (node (ref "PB11") (pin "1") (pinfunction "Pad_1") (pintype "unspecified"))
      (node (ref "U39") (pin "1") (pinfunction "1_1") (pintype "unspecified"))
    )
    (net (code "45") (name "Net-(P12-Pad)") (class "Default")
      (node (ref "P12") (pin "1") (pinfunction "Pad_1") (pintype "unspecified"))
      (node (ref "PA12") (pin "1") (pinfunction "Pad_1") (pintype "unspecified"))
      (node (ref "PB12") (pin "1") (pinfunction "Pad_1") (pintype "unspecified"))
      (node (ref "U40") (pin "1") (pinfunction "1_1") (pintype "unspecified"))
    )
    (net (code "46") (name "Net-(P13-Pad)") (class "Default")
      (node (ref "P13") (pin "1") (pinfunction "Pad_1") (pintype "unspecified"))
      (node (ref "PA13") (pin "1") (pinfunction "Pad_1") (pintype "unspecified"))
      (node (ref "PB13") (pin "1") (pinfunction "Pad_1") (pintype "unspecified"))
      (node (ref "U41") (pin "1") (pinfunction "1_1") (pintype "unspecified"))
    )
    (net (code "47") (name "Net-(P14-Pad)") (class "Default")
      (node (ref "P14") (pin "1") (pinfunction "Pad_1") (pintype "unspecified"))
      (node (ref "PA14") (pin "1") (pinfunction "Pad_1") (pintype "unspecified"))
      (node (ref "PB14") (pin "1") (pinfunction "Pad_1") (pintype "unspecified"))
      (node (ref "U42") (pin "1") (pinfunction "1_1") (pintype "unspecified"))
    )
    (net (code "48") (name "Net-(P15-Pad)") (class "Default")
      (node (ref "P15") (pin "1") (pinfunction "Pad_1") (pintype "unspecified"))
      (node (ref "PA15") (pin "1") (pinfunction "Pad_1") (pintype "unspecified"))
      (node (ref "PB15") (pin "1") (pinfunction "Pad_1") (pintype "unspecified"))
      (node (ref "U43") (pin "1") (pinfunction "1_1") (pintype "unspecified"))
    )
    (net (code "49") (name "Net-(P16-Pad)") (class "Default")
      (node (ref "P16") (pin "1") (pinfunction "Pad_1") (pintype "unspecified"))
      (node (ref "PA16") (pin "1") (pinfunction "Pad_1") (pintype "unspecified"))
      (node (ref "PB16") (pin "1") (pinfunction "Pad_1") (pintype "unspecified"))
      (node (ref "U44") (pin "1") (pinfunction "1_1") (pintype "unspecified"))
    )
    (net (code "50") (name "Net-(P17-Pad)") (class "Default")
      (node (ref "P17") (pin "1") (pinfunction "Pad_1") (pintype "unspecified"))
      (node (ref "PA17") (pin "1") (pinfunction "Pad_1") (pintype "unspecified"))
      (node (ref "PB17") (pin "1") (pinfunction "Pad_1") (pintype "unspecified"))
      (node (ref "U45") (pin "1") (pinfunction "1_1") (pintype "unspecified"))
    )
    (net (code "51") (name "Net-(P18-Pad)") (class "Default")
      (node (ref "P18") (pin "1") (pinfunction "Pad_1") (pintype "unspecified"))
      (node (ref "PA18") (pin "1") (pinfunction "Pad_1") (pintype "unspecified"))
      (node (ref "PB18") (pin "1") (pinfunction "Pad_1") (pintype "unspecified"))
      (node (ref "U46") (pin "1") (pinfunction "1_1") (pintype "unspecified"))
    )
    (net (code "52") (name "Net-(P19-Pad)") (class "Default")
      (node (ref "P19") (pin "1") (pinfunction "Pad_1") (pintype "unspecified"))
      (node (ref "PA19") (pin "1") (pinfunction "Pad_1") (pintype "unspecified"))
      (node (ref "PB19") (pin "1") (pinfunction "Pad_1") (pintype "unspecified"))
      (node (ref "U47") (pin "1") (pinfunction "1_1") (pintype "unspecified"))
    )
    (net (code "53") (name "Net-(P20-Pad)") (class "Default")
      (node (ref "P20") (pin "1") (pinfunction "Pad_1") (pintype "unspecified"))
      (node (ref "PA20") (pin "1") (pinfunction "Pad_1") (pintype "unspecified"))
      (node (ref "PB20") (pin "1") (pinfunction "Pad_1") (pintype "unspecified"))
      (node (ref "U48") (pin "1") (pinfunction "1_1") (pintype "unspecified"))
    )
    (net (code "54") (name "Net-(P21-Pad)") (class "Default")
      (node (ref "P21") (pin "1") (pinfunction "Pad_1") (pintype "unspecified"))
      (node (ref "PA21") (pin "1") (pinfunction "Pad_1") (pintype "unspecified"))
      (node (ref "PB21") (pin "1") (pinfunction "Pad_1") (pintype "unspecified"))
      (node (ref "U49") (pin "1") (pinfunction "1_1") (pintype "unspecified"))
    )
    (net (code "55") (name "Net-(P22-Pad)") (class "Default")
      (node (ref "P22") (pin "1") (pinfunction "Pad_1") (pintype "unspecified"))
      (node (ref "PA22") (pin "1") (pinfunction "Pad_1") (pintype "unspecified"))
      (node (ref "PB22") (pin "1") (pinfunction "Pad_1") (pintype "unspecified"))
      (node (ref "U50") (pin "1") (pinfunction "1_1") (pintype "unspecified"))
    )
    (net (code "56") (name "Net-(P23-Pad)") (class "Default")
      (node (ref "P23") (pin "1") (pinfunction "Pad_1") (pintype "unspecified"))
      (node (ref "PA23") (pin "1") (pinfunction "Pad_1") (pintype "unspecified"))
      (node (ref "PB23") (pin "1") (pinfunction "Pad_1") (pintype "unspecified"))
      (node (ref "U51") (pin "1") (pinfunction "1_1") (pintype "unspecified"))
    )
    (net (code "57") (name "Net-(P24-Pad)") (class "Default")
      (node (ref "P24") (pin "1") (pinfunction "Pad_1") (pintype "unspecified"))
      (node (ref "PA24") (pin "1") (pinfunction "Pad_1") (pintype "unspecified"))
      (node (ref "PB24") (pin "1") (pinfunction "Pad_1") (pintype "unspecified"))
      (node (ref "U52") (pin "1") (pinfunction "1_1") (pintype "unspecified"))
    )
    (net (code "58") (name "Net-(P25-Pad)") (class "Default")
      (node (ref "P25") (pin "1") (pinfunction "Pad_1") (pintype "unspecified"))
      (node (ref "PA25") (pin "1") (pinfunction "Pad_1") (pintype "unspecified"))
      (node (ref "PB25") (pin "1") (pinfunction "Pad_1") (pintype "unspecified"))
      (node (ref "U53") (pin "1") (pinfunction "1_1") (pintype "unspecified"))
    )
    (net (code "59") (name "Net-(P26-Pad)") (class "Default")
      (node (ref "P26") (pin "1") (pinfunction "Pad_1") (pintype "unspecified"))
      (node (ref "PA26") (pin "1") (pinfunction "Pad_1") (pintype "unspecified"))
      (node (ref "PB26") (pin "1") (pinfunction "Pad_1") (pintype "unspecified"))
      (node (ref "U54") (pin "1") (pinfunction "1_1") (pintype "unspecified"))
    )
    (net (code "60") (name "Net-(P27-Pad)") (class "Default")
      (node (ref "P27") (pin "1") (pinfunction "Pad_1") (pintype "unspecified"))
      (node (ref "PA27") (pin "1") (pinfunction "Pad_1") (pintype "unspecified"))
      (node (ref "PB27") (pin "1") (pinfunction "Pad_1") (pintype "unspecified"))
      (node (ref "U55") (pin "1") (pinfunction "1_1") (pintype "unspecified"))
    )
    (net (code "61") (name "Net-(P28-Pad)") (class "Default")
      (node (ref "P28") (pin "1") (pinfunction "Pad_1") (pintype "unspecified"))
      (node (ref "PA28") (pin "1") (pinfunction "Pad_1") (pintype "unspecified"))
      (node (ref "PB28") (pin "1") (pinfunction "Pad_1") (pintype "unspecified"))
      (node (ref "U56") (pin "1") (pinfunction "1_1") (pintype "unspecified"))
    )
    (net (code "62") (name "Net-(P29-Pad)") (class "Default")
      (node (ref "P29") (pin "1") (pinfunction "Pad_1") (pintype "unspecified"))
      (node (ref "PA29") (pin "1") (pinfunction "Pad_1") (pintype "unspecified"))
      (node (ref "PB29") (pin "1") (pinfunction "Pad_1") (pintype "unspecified"))
      (node (ref "U57") (pin "1") (pinfunction "1_1") (pintype "unspecified"))
    )
    (net (code "63") (name "Net-(P30-Pad)") (class "Default")
      (node (ref "P30") (pin "1") (pinfunction "Pad_1") (pintype "unspecified"))
      (node (ref "PA30") (pin "1") (pinfunction "Pad_1") (pintype "unspecified"))
      (node (ref "PB30") (pin "1") (pinfunction "Pad_1") (pintype "unspecified"))
      (node (ref "U58") (pin "1") (pinfunction "1_1") (pintype "unspecified"))
    )
    (net (code "64") (name "Net-(P31-Pad)") (class "Default")
      (node (ref "P31") (pin "1") (pinfunction "Pad_1") (pintype "unspecified"))
      (node (ref "PA31") (pin "1") (pinfunction "Pad_1") (pintype "unspecified"))
      (node (ref "PB31") (pin "1") (pinfunction "Pad_1") (pintype "unspecified"))
      (node (ref "U59") (pin "1") (pinfunction "1_1") (pintype "unspecified"))
    )
    (net (code "65") (name "Net-(P32-Pad)") (class "Default")
      (node (ref "P32") (pin "1") (pinfunction "Pad_1") (pintype "unspecified"))
      (node (ref "PA32") (pin "1") (pinfunction "Pad_1") (pintype "unspecified"))
      (node (ref "PB32") (pin "1") (pinfunction "Pad_1") (pintype "unspecified"))
      (node (ref "U60") (pin "1") (pinfunction "1_1") (pintype "unspecified"))
    )
    (net (code "66") (name "Net-(P33-Pad)") (class "Default")
      (node (ref "P33") (pin "1") (pinfunction "Pad_1") (pintype "unspecified"))
      (node (ref "PB33") (pin "1") (pinfunction "Pad_1") (pintype "unspecified"))
      (node (ref "U61") (pin "1") (pinfunction "1_1") (pintype "unspecified"))
    )
    (net (code "67") (name "Net-(P34-Pad)") (class "Default")
      (node (ref "P34") (pin "1") (pinfunction "Pad_1") (pintype "unspecified"))
      (node (ref "PB34") (pin "1") (pinfunction "Pad_1") (pintype "unspecified"))
      (node (ref "U62") (pin "1") (pinfunction "1_1") (pintype "unspecified"))
    )
    (net (code "68") (name "Net-(P35-Pad)") (class "Default")
      (node (ref "P35") (pin "1") (pinfunction "Pad_1") (pintype "unspecified"))
      (node (ref "PB35") (pin "1") (pinfunction "Pad_1") (pintype "unspecified"))
      (node (ref "U63") (pin "1") (pinfunction "1_1") (pintype "unspecified"))
    )
    (net (code "69") (name "Net-(P36-Pad)") (class "Default")
      (node (ref "P36") (pin "1") (pinfunction "Pad_1") (pintype "unspecified"))
      (node (ref "PB36") (pin "1") (pinfunction "Pad_1") (pintype "unspecified"))
      (node (ref "U64") (pin "1") (pinfunction "1_1") (pintype "unspecified"))
    )
    (net (code "70") (name "Net-(P37-Pad)") (class "Default")
      (node (ref "P37") (pin "1") (pinfunction "Pad_1") (pintype "unspecified"))
      (node (ref "PB37") (pin "1") (pinfunction "Pad_1") (pintype "unspecified"))
      (node (ref "U65") (pin "1") (pinfunction "1_1") (pintype "unspecified"))
    )
    (net (code "71") (name "Net-(R10-Pad2)") (class "Default")
      (node (ref "R10") (pin "2") (pinfunction "2_2") (pintype "unspecified"))
      (node (ref "R11") (pin "3") (pinfunction "3_3") (pintype "input"))
    )
    (net (code "72") (name "Net-(R11-Pad2)") (class "Default")
      (node (ref "R11") (pin "2") (pinfunction "2_2") (pintype "input"))
      (node (ref "R12") (pin "1") (pinfunction "1_1") (pintype "unspecified"))
      (node (ref "R14") (pin "2") (pinfunction "2_2") (pintype "unspecified"))
    )
    (net (code "73") (name "Net-(U67-+)") (class "Default")
      (node (ref "R13") (pin "2") (pinfunction "2_2") (pintype "unspecified"))
      (node (ref "R14") (pin "1") (pinfunction "1_1") (pintype "unspecified"))
      (node (ref "U67") (pin "1") (pinfunction "+_1") (pintype "input"))
    )
    (net (code "74") (name "Net-(U67-OUT)") (class "Default")
      (node (ref "R13") (pin "1") (pinfunction "1_1") (pintype "unspecified"))
      (node (ref "R9") (pin "2") (pinfunction "2_2") (pintype "unspecified"))
      (node (ref "U67") (pin "4") (pinfunction "OUT_4") (pintype "output"))
    )
    (net (code "75") (name "PWM-F") (class "Default")
      (node (ref "IC1") (pin "3") (pinfunction "OUTPUT_3") (pintype "unspecified"))
      (node (ref "IC2") (pin "2") (pinfunction "INA_2") (pintype "unspecified"))
      (node (ref "PWM") (pin "1") (pinfunction "1_1") (pintype "unspecified"))
      (node (ref "Q1") (pin "1") (pinfunction "G_1") (pintype "unspecified"))
      (node (ref "R4") (pin "2") (pinfunction "2_2") (pintype "unspecified"))
    )
    (net (code "76") (name "SG1{slash}KS1") (class "Default")
      (node (ref "IC4") (pin "14") (pinfunction "SG1_14") (pintype "unspecified"))
      (node (ref "U1") (pin "1") (pinfunction "1_1") (pintype "unspecified"))
    )
    (net (code "77") (name "SG2{slash}KS2") (class "Default")
      (node (ref "IC4") (pin "15") (pinfunction "SG2_15") (pintype "unspecified"))
      (node (ref "U2") (pin "1") (pinfunction "1_1") (pintype "unspecified"))
    )
    (net (code "78") (name "SG3{slash}KS3") (class "Default")
      (node (ref "IC4") (pin "16") (pinfunction "SG3_16") (pintype "unspecified"))
      (node (ref "U3") (pin "1") (pinfunction "1_1") (pintype "unspecified"))
    )
    (net (code "79") (name "SG4{slash}KS4") (class "Default")
      (node (ref "IC4") (pin "17") (pinfunction "SG4_17") (pintype "unspecified"))
      (node (ref "U4") (pin "1") (pinfunction "1_1") (pintype "unspecified"))
    )
    (net (code "80") (name "SG5{slash}KS5") (class "Default")
      (node (ref "IC4") (pin "18") (pinfunction "SG5_18") (pintype "unspecified"))
      (node (ref "U5") (pin "1") (pinfunction "1_1") (pintype "unspecified"))
    )
    (net (code "81") (name "SG6{slash}KS6") (class "Default")
      (node (ref "IC4") (pin "19") (pinfunction "SG6_19") (pintype "unspecified"))
      (node (ref "U6") (pin "1") (pinfunction "1_1") (pintype "unspecified"))
    )
    (net (code "82") (name "SG7{slash}KS7") (class "Default")
      (node (ref "IC4") (pin "20") (pinfunction "SG7_20") (pintype "unspecified"))
      (node (ref "U7") (pin "1") (pinfunction "1_1") (pintype "unspecified"))
    )
    (net (code "83") (name "SG8{slash}KS8") (class "Default")
      (node (ref "IC4") (pin "21") (pinfunction "SG8_21") (pintype "unspecified"))
      (node (ref "U8") (pin "1") (pinfunction "1_1") (pintype "unspecified"))
    )
    (net (code "84") (name "SG9{slash}KS9") (class "Default")
      (node (ref "IC4") (pin "22") (pinfunction "SG9_22") (pintype "unspecified"))
      (node (ref "U9") (pin "1") (pinfunction "1_1") (pintype "unspecified"))
    )
    (net (code "85") (name "SG10{slash}KS10") (class "Default")
      (node (ref "IC4") (pin "23") (pinfunction "SG10_23") (pintype "unspecified"))
      (node (ref "U10") (pin "1") (pinfunction "1_1") (pintype "unspecified"))
    )
    (net (code "86") (name "SG11{slash}KS11") (class "Default")
      (node (ref "IC4") (pin "24") (pinfunction "SG11_24") (pintype "unspecified"))
      (node (ref "U11") (pin "1") (pinfunction "1_1") (pintype "unspecified"))
    )
    (net (code "87") (name "SG12{slash}KS12") (class "Default")
      (node (ref "IC4") (pin "25") (pinfunction "SG12_25") (pintype "unspecified"))
      (node (ref "U12") (pin "1") (pinfunction "1_1") (pintype "unspecified"))
    )
    (net (code "88") (name "SG13{slash}KS13") (class "Default")
      (node (ref "IC4") (pin "26") (pinfunction "SG13_26") (pintype "unspecified"))
      (node (ref "U13") (pin "1") (pinfunction "1_1") (pintype "unspecified"))
    )
    (net (code "89") (name "SG14{slash}KS14") (class "Default")
      (node (ref "IC4") (pin "27") (pinfunction "SG14_27") (pintype "unspecified"))
      (node (ref "U14") (pin "1") (pinfunction "1_1") (pintype "unspecified"))
    )
    (net (code "90") (name "SG15{slash}KS15") (class "Default")
      (node (ref "IC4") (pin "28") (pinfunction "SG15_28") (pintype "unspecified"))
      (node (ref "U15") (pin "1") (pinfunction "1_1") (pintype "unspecified"))
    )
    (net (code "91") (name "SG16{slash}KS16") (class "Default")
      (node (ref "IC4") (pin "29") (pinfunction "SG16_29") (pintype "unspecified"))
      (node (ref "U16") (pin "1") (pinfunction "1_1") (pintype "unspecified"))
    )
    (net (code "92") (name "SG17{slash}GR12") (class "Default")
      (node (ref "IC4") (pin "31") (pinfunction "SG17_31") (pintype "unspecified"))
      (node (ref "U17") (pin "1") (pinfunction "1_1") (pintype "unspecified"))
    )
    (net (code "93") (name "SG18{slash}GR11") (class "Default")
      (node (ref "IC4") (pin "32") (pinfunction "SG18_32") (pintype "unspecified"))
      (node (ref "U18") (pin "1") (pinfunction "1_1") (pintype "unspecified"))
    )
    (net (code "94") (name "SG19{slash}GR10") (class "Default")
      (node (ref "IC4") (pin "33") (pinfunction "SG19_33") (pintype "unspecified"))
      (node (ref "U19") (pin "1") (pinfunction "1_1") (pintype "unspecified"))
    )
    (net (code "95") (name "SG20{slash}GR9") (class "Default")
      (node (ref "IC4") (pin "34") (pinfunction "SG20_34") (pintype "unspecified"))
      (node (ref "U20") (pin "1") (pinfunction "1_1") (pintype "unspecified"))
    )
    (net (code "96") (name "SG21{slash}GR8") (class "Default")
      (node (ref "IC4") (pin "35") (pinfunction "GR8_35") (pintype "unspecified"))
      (node (ref "U28") (pin "1") (pinfunction "1_1") (pintype "unspecified"))
    )
    (net (code "97") (name "SG22{slash}GR7") (class "Default")
      (node (ref "IC4") (pin "36") (pinfunction "GR7_36") (pintype "unspecified"))
      (node (ref "U27") (pin "1") (pinfunction "1_1") (pintype "unspecified"))
    )
    (net (code "98") (name "SG23{slash}GR6") (class "Default")
      (node (ref "IC4") (pin "37") (pinfunction "GR6_37") (pintype "unspecified"))
      (node (ref "U26") (pin "1") (pinfunction "1_1") (pintype "unspecified"))
    )
    (net (code "99") (name "SG24{slash}GR5") (class "Default")
      (node (ref "IC4") (pin "38") (pinfunction "GR5_38") (pintype "unspecified"))
      (node (ref "U25") (pin "1") (pinfunction "1_1") (pintype "unspecified"))
    )
    (net (code "100") (name "STB") (class "Default")
      (node (ref "R17") (pin "1") (pinfunction "1_1") (pintype "unspecified"))
      (node (ref "STB") (pin "1") (pinfunction "1_1") (pintype "unspecified"))
    )
    (net (code "101") (name "VH") (class "Default")
      (node (ref "C14") (pin "2") (pinfunction "2_2") (pintype "input"))
      (node (ref "D1") (pin "2") (pinfunction "A_2") (pintype "unspecified"))
      (node (ref "IC4") (pin "30") (pinfunction "VEE_30") (pintype "unspecified"))
      (node (ref "L2") (pin "2") (pinfunction "2_2") (pintype "unspecified"))
      (node (ref "R10") (pin "1") (pinfunction "1_1") (pintype "unspecified"))
      (node (ref "VH") (pin "1") (pinfunction "1_1") (pintype "unspecified"))
    )
    (net (code "102") (name "unconnected-(IC3-NC-Pad6)") (class "Default")
      (node (ref "IC3") (pin "6") (pinfunction "NC_6") (pintype "unspecified+no_connect"))
    )
    (net (code "103") (name "unconnected-(IC4-K1-Pad10)") (class "Default")
      (node (ref "IC4") (pin "10") (pinfunction "K1_10") (pintype "unspecified"))
    )
    (net (code "104") (name "unconnected-(IC4-K2-Pad11)") (class "Default")
      (node (ref "IC4") (pin "11") (pinfunction "K2_11") (pintype "unspecified"))
    )
    (net (code "105") (name "unconnected-(R11-Pad1)") (class "Default")
      (node (ref "R11") (pin "1") (pinfunction "1_1") (pintype "input"))
    )
  )
)
